# untitled.net
KiCad netlist of a schematic drawn in EAGLE
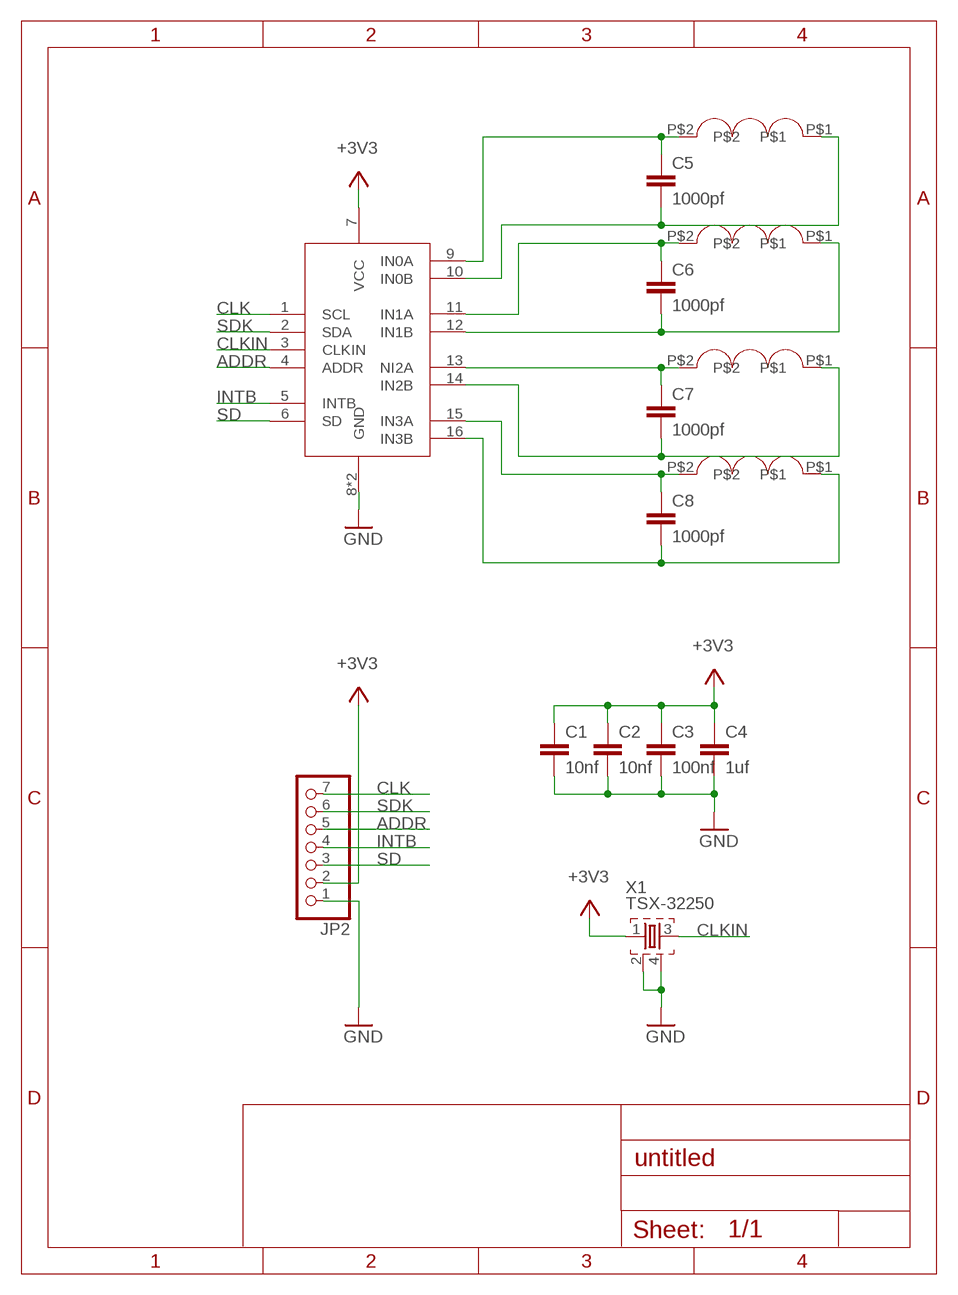
[diagram p0: schematic, sheet 1]

(export (version "E")
  (design (tool "Eeschema 10.0.6"))
  (components
    (comp (ref "C1")
      (value "10nf")
      (footprint "eagle-import:C0603")
      (libsource (lib "eagle-import") (part "C-EUC0603"))
    )
    (comp (ref "C2")
      (value "10nf")
      (footprint "eagle-import:C0603")
      (libsource (lib "eagle-import") (part "C-EUC0603"))
    )
    (comp (ref "C3")
      (value "100nf")
      (footprint "eagle-import:C0603")
      (libsource (lib "eagle-import") (part "C-EUC0603"))
    )
    (comp (ref "C4")
      (value "1uf")
      (footprint "eagle-import:C0603")
      (libsource (lib "eagle-import") (part "C-EUC0603"))
    )
    (comp (ref "C5")
      (value "1000pf")
      (footprint "eagle-import:C0603")
      (libsource (lib "eagle-import") (part "C-EUC0603"))
    )
    (comp (ref "C6")
      (value "1000pf")
      (footprint "eagle-import:C0603")
      (libsource (lib "eagle-import") (part "C-EUC0603"))
    )
    (comp (ref "C7")
      (value "1000pf")
      (footprint "eagle-import:C0603")
      (libsource (lib "eagle-import") (part "C-EUC0603"))
    )
    (comp (ref "C8")
      (value "1000pf")
      (footprint "eagle-import:C0603")
      (libsource (lib "eagle-import") (part "C-EUC0603"))
    )
    (comp (ref "JP2")
      (value "PINHD-1X7")
      (footprint "eagle-import:1X07")
      (libsource (lib "eagle-import") (part "PINHD-1X7"))
    )
    (comp (ref "U$1")
      (value "LDC1314")
      (footprint "eagle-import:QFN50P400X400X80-17N")
      (libsource (lib "eagle-import") (part "LDC1314"))
    )
    (comp (ref "U$2")
      (value "COIL")
      (footprint "eagle-import:L19.18.2")
      (libsource (lib "eagle-import") (part "COIL"))
    )
    (comp (ref "U$3")
      (value "COIL")
      (footprint "eagle-import:L19.18.2")
      (libsource (lib "eagle-import") (part "COIL"))
    )
    (comp (ref "U$4")
      (value "COIL")
      (footprint "eagle-import:L19.18.2")
      (libsource (lib "eagle-import") (part "COIL"))
    )
    (comp (ref "U$5")
      (value "COIL")
      (footprint "eagle-import:L19.18.2")
      (libsource (lib "eagle-import") (part "COIL"))
    )
    (comp (ref "X1")
      (value "TSX-32250")
      (footprint "eagle-import:TSX-3225")
      (fields (field (name "MF") "EPSON") (field (name "MP") "TSX-3225"))
      (libsource (lib "eagle-import") (part "TSX-32250"))
    )
  )
  (nets
    (net (code "1") (name "+3V3") (class "Default")
      (node (ref "C1") (pin "1") (pinfunction "1_1") (pintype "passive"))
      (node (ref "C2") (pin "1") (pinfunction "1_1") (pintype "passive"))
      (node (ref "C3") (pin "1") (pinfunction "1_1") (pintype "passive"))
      (node (ref "C4") (pin "1") (pinfunction "1_1") (pintype "passive"))
      (node (ref "JP2") (pin "2") (pinfunction "2_2") (pintype "passive"))
      (node (ref "U$1") (pin "7") (pinfunction "VCC_7") (pintype "bidirectional"))
      (node (ref "X1") (pin "1") (pinfunction "1_1") (pintype "passive"))
    )
    (net (code "2") (name "/ADDR") (class "Default")
      (node (ref "JP2") (pin "5") (pinfunction "5_5") (pintype "passive"))
      (node (ref "U$1") (pin "4") (pinfunction "ADDR_4") (pintype "bidirectional"))
    )
    (net (code "3") (name "/CLK") (class "Default")
      (node (ref "JP2") (pin "7") (pinfunction "7_7") (pintype "passive"))
      (node (ref "U$1") (pin "1") (pinfunction "SCL_1") (pintype "bidirectional"))
    )
    (net (code "4") (name "/CLKIN") (class "Default")
      (node (ref "U$1") (pin "3") (pinfunction "CLKIN_3") (pintype "bidirectional"))
      (node (ref "X1") (pin "3") (pinfunction "3_3") (pintype "passive"))
    )
    (net (code "5") (name "/INTB") (class "Default")
      (node (ref "JP2") (pin "4") (pinfunction "4_4") (pintype "passive"))
      (node (ref "U$1") (pin "5") (pinfunction "INTB_5") (pintype "bidirectional"))
    )
    (net (code "6") (name "/SD") (class "Default")
      (node (ref "JP2") (pin "3") (pinfunction "3_3") (pintype "passive"))
      (node (ref "U$1") (pin "6") (pinfunction "SD_6") (pintype "bidirectional"))
    )
    (net (code "7") (name "/SDK") (class "Default")
      (node (ref "JP2") (pin "6") (pinfunction "6_6") (pintype "passive"))
      (node (ref "U$1") (pin "2") (pinfunction "SDA_2") (pintype "bidirectional"))
    )
    (net (code "8") (name "GND") (class "Default")
      (node (ref "C1") (pin "2") (pinfunction "2_2") (pintype "passive"))
      (node (ref "C2") (pin "2") (pinfunction "2_2") (pintype "passive"))
      (node (ref "C3") (pin "2") (pinfunction "2_2") (pintype "passive"))
      (node (ref "C4") (pin "2") (pinfunction "2_2") (pintype "passive"))
      (node (ref "JP2") (pin "1") (pinfunction "1_1") (pintype "passive"))
      (node (ref "U$1") (pin "17") (pinfunction "GND_17") (pintype "bidirectional"))
      (node (ref "U$1") (pin "8") (pinfunction "GND_8") (pintype "bidirectional"))
      (node (ref "X1") (pin "2") (pinfunction "2_2") (pintype "passive"))
      (node (ref "X1") (pin "4") (pinfunction "4_4") (pintype "passive"))
    )
    (net (code "9") (name "Net-(U$1-IN0A)") (class "Default")
      (node (ref "C5") (pin "1") (pinfunction "1_1") (pintype "passive"))
      (node (ref "U$1") (pin "9") (pinfunction "IN0A_9") (pintype "bidirectional"))
      (node (ref "U$2") (pin "P$2") (pinfunction "P$2_P$2") (pintype "output"))
    )
    (net (code "10") (name "Net-(U$1-IN0B)") (class "Default")
      (node (ref "C5") (pin "2") (pinfunction "2_2") (pintype "passive"))
      (node (ref "U$1") (pin "10") (pinfunction "IN0B_10") (pintype "bidirectional"))
      (node (ref "U$2") (pin "P$1") (pinfunction "P$1_P$1") (pintype "bidirectional"))
    )
    (net (code "11") (name "Net-(U$1-IN1A)") (class "Default")
      (node (ref "C6") (pin "1") (pinfunction "1_1") (pintype "passive"))
      (node (ref "U$1") (pin "11") (pinfunction "IN1A_11") (pintype "bidirectional"))
      (node (ref "U$3") (pin "P$2") (pinfunction "P$2_P$2") (pintype "output"))
    )
    (net (code "12") (name "Net-(U$1-IN1B)") (class "Default")
      (node (ref "C6") (pin "2") (pinfunction "2_2") (pintype "passive"))
      (node (ref "U$1") (pin "12") (pinfunction "IN1B_12") (pintype "bidirectional"))
      (node (ref "U$3") (pin "P$1") (pinfunction "P$1_P$1") (pintype "bidirectional"))
    )
    (net (code "13") (name "Net-(U$1-IN2B)") (class "Default")
      (node (ref "C7") (pin "2") (pinfunction "2_2") (pintype "passive"))
      (node (ref "U$1") (pin "14") (pinfunction "IN2B_14") (pintype "bidirectional"))
      (node (ref "U$4") (pin "P$1") (pinfunction "P$1_P$1") (pintype "bidirectional"))
    )
    (net (code "14") (name "Net-(U$1-IN3A)") (class "Default")
      (node (ref "C8") (pin "1") (pinfunction "1_1") (pintype "passive"))
      (node (ref "U$1") (pin "15") (pinfunction "IN3A_15") (pintype "bidirectional"))
      (node (ref "U$5") (pin "P$2") (pinfunction "P$2_P$2") (pintype "output"))
    )
    (net (code "15") (name "Net-(U$1-IN3B)") (class "Default")
      (node (ref "C8") (pin "2") (pinfunction "2_2") (pintype "passive"))
      (node (ref "U$1") (pin "16") (pinfunction "IN3B_16") (pintype "bidirectional"))
      (node (ref "U$5") (pin "P$1") (pinfunction "P$1_P$1") (pintype "bidirectional"))
    )
    (net (code "16") (name "Net-(U$1-NI2A)") (class "Default")
      (node (ref "C7") (pin "1") (pinfunction "1_1") (pintype "passive"))
      (node (ref "U$1") (pin "13") (pinfunction "NI2A_13") (pintype "bidirectional"))
      (node (ref "U$4") (pin "P$2") (pinfunction "P$2_P$2") (pintype "output"))
    )
  )
)
